# Microcontroller.net
KiCad netlist of a schematic drawn in Altium Designer
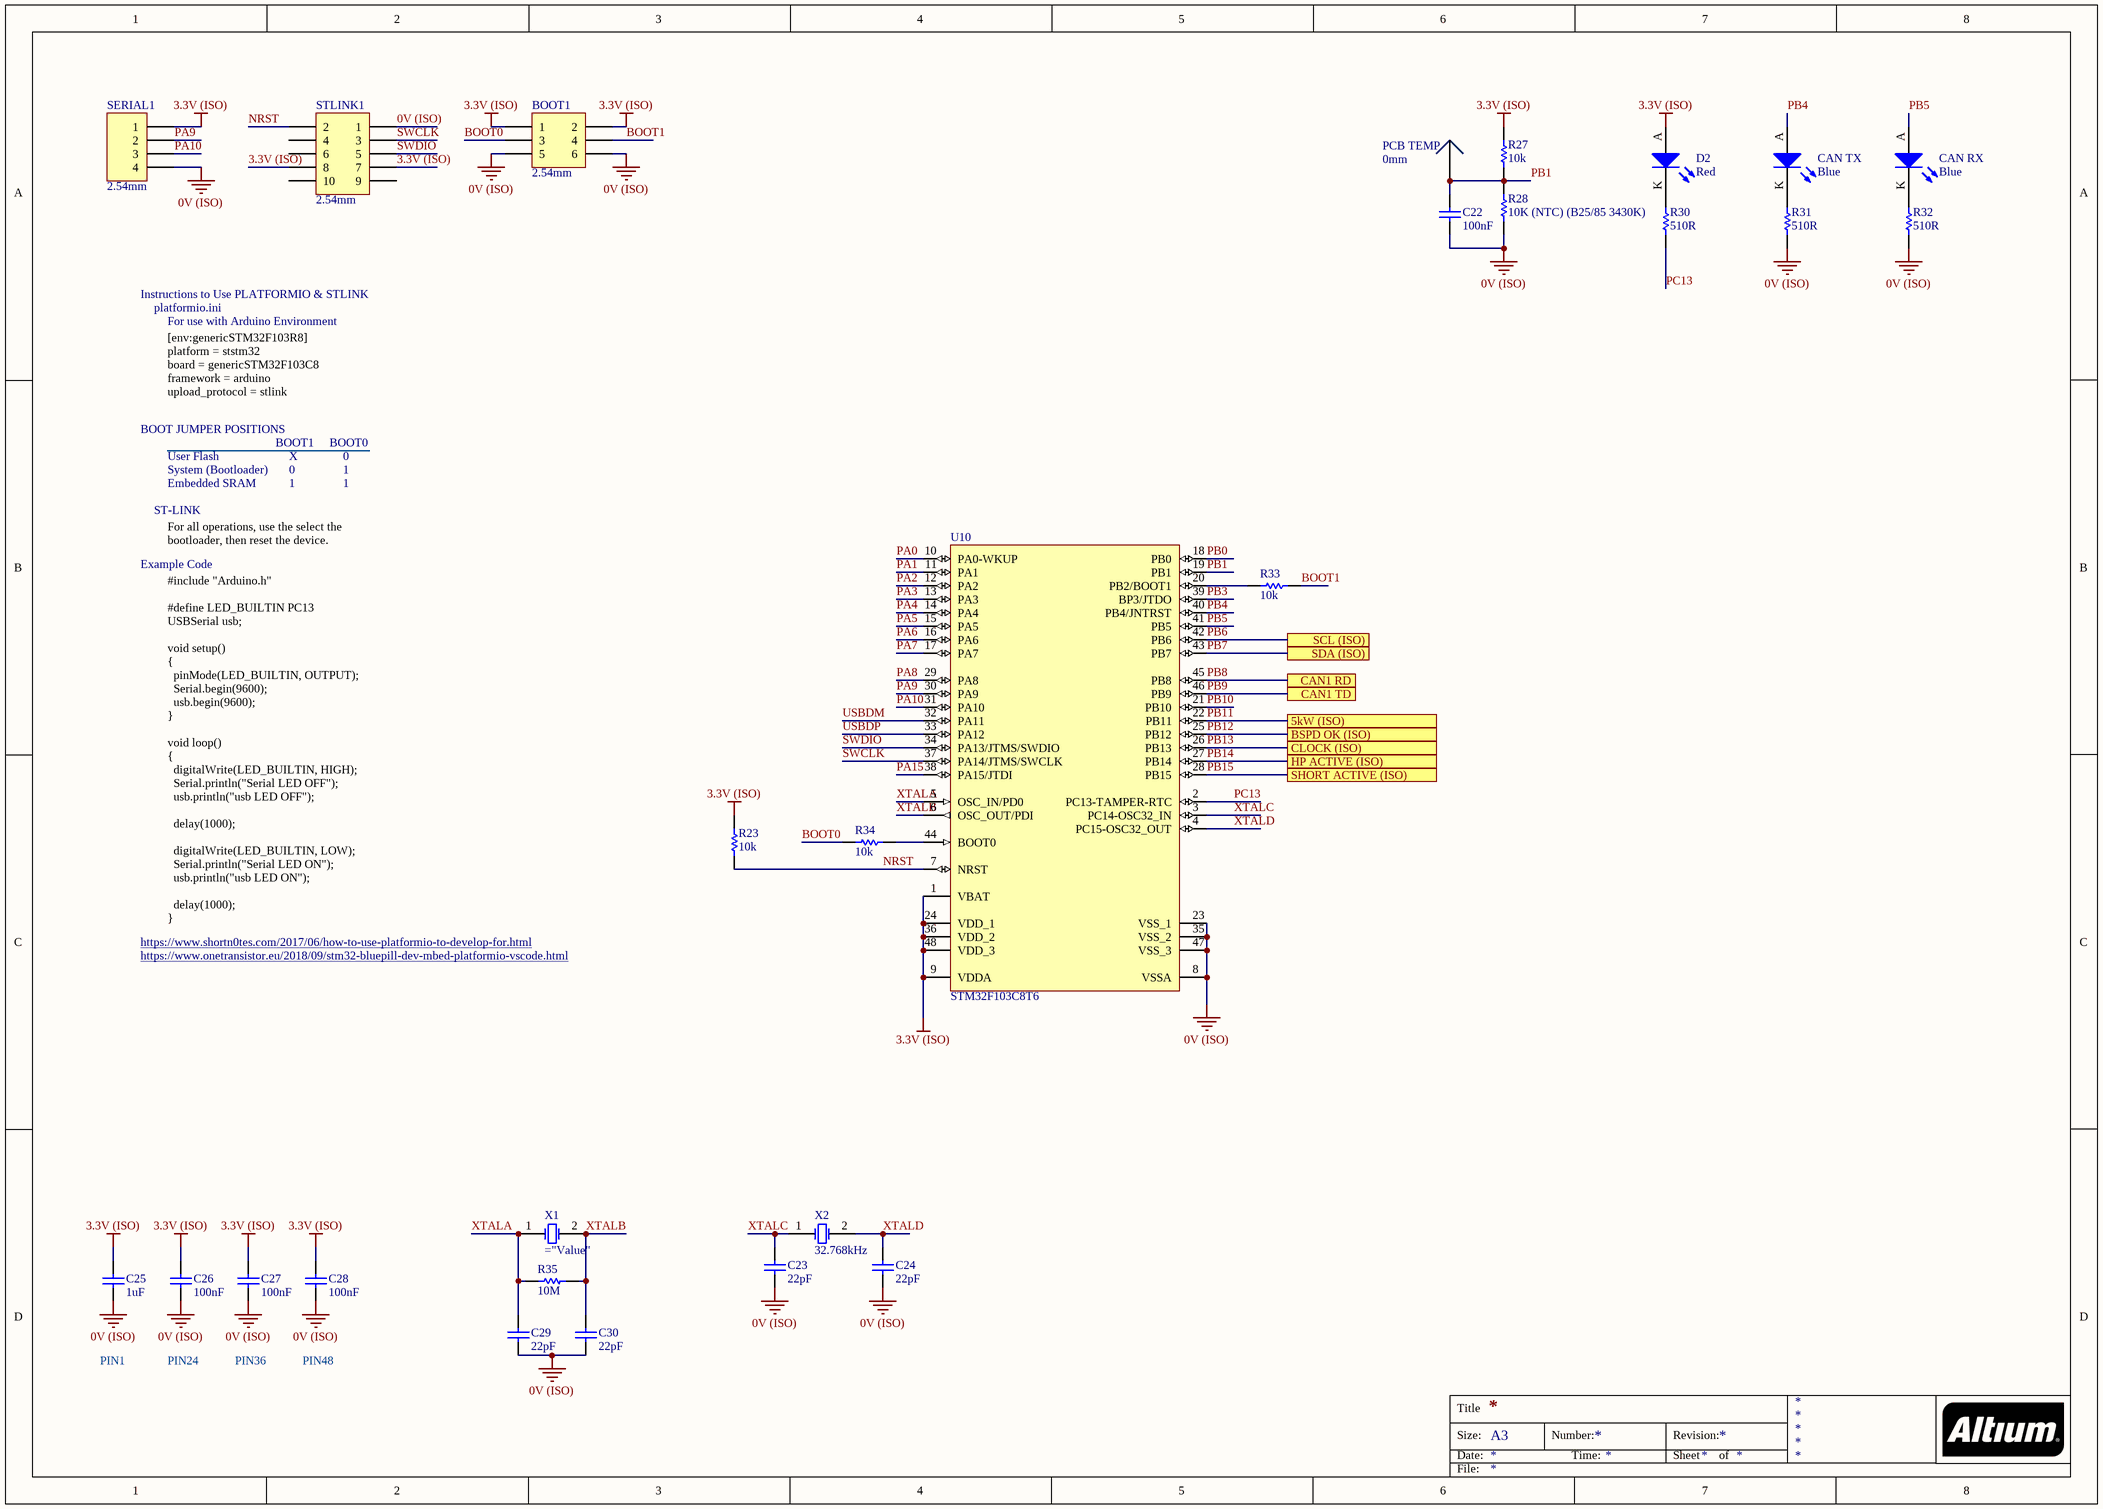
[diagram p0: Microcontroller.SchDoc]

(export (version "E")
  (design (tool "Eeschema 10.0.6"))
  (components
    (comp (ref "BOOT1")
      (value "2.54mm")
      (footprint "TH 2.54mm Header 2x3")
      (fields (field (name "PART NUMBER") "TH 2.54mm Header 2x3") (field (name "CONTACT") "NA"))
      (libsource (lib "ts_20-standard-connectors") (part "Header 2x3"))
    )
    (comp (ref "C22")
      (value "100nF")
      (footprint "0805")
      (fields
        (field (name "PART NUMBER") "GCM21BR71E104KA37L")
        (field (name "TOLERANCE") "10%")
        (field (name "MANUFACTURER") "muRata")
      )
      (libsource (lib "ts_20-standard-library") (part "Capacitor"))
    )
    (comp (ref "C23")
      (value "22pF")
      (footprint "0805")
      (fields
        (field (name "PART NUMBER") "GCM21B5C1H220JA37L")
        (field (name "TOLERANCE") "5%")
        (field (name "MANUFACTURER") "muRata")
      )
      (libsource (lib "ts_20-standard-library") (part "Capacitor"))
    )
    (comp (ref "C24")
      (value "22pF")
      (footprint "0805")
      (fields
        (field (name "PART NUMBER") "GCM21B5C1H220JA37L")
        (field (name "TOLERANCE") "5%")
        (field (name "MANUFACTURER") "muRata")
      )
      (libsource (lib "ts_20-standard-library") (part "Capacitor"))
    )
    (comp (ref "C25")
      (value "1uF")
      (footprint "0805")
      (fields
        (field (name "PART NUMBER") "GCM21BR71A105KA37L")
        (field (name "TOLERANCE") "10%")
        (field (name "MANUFACTURER") "muRata")
      )
      (libsource (lib "ts_20-standard-library") (part "Capacitor"))
    )
    (comp (ref "C26")
      (value "100nF")
      (footprint "0805")
      (fields
        (field (name "PART NUMBER") "GCM21BR71E104KA37L")
        (field (name "TOLERANCE") "10%")
        (field (name "MANUFACTURER") "muRata")
      )
      (libsource (lib "ts_20-standard-library") (part "Capacitor"))
    )
    (comp (ref "C27")
      (value "100nF")
      (footprint "0805")
      (fields
        (field (name "PART NUMBER") "GCM21BR71E104KA37L")
        (field (name "TOLERANCE") "10%")
        (field (name "MANUFACTURER") "muRata")
      )
      (libsource (lib "ts_20-standard-library") (part "Capacitor"))
    )
    (comp (ref "C28")
      (value "100nF")
      (footprint "0805")
      (fields
        (field (name "PART NUMBER") "GCM21BR71E104KA37L")
        (field (name "TOLERANCE") "10%")
        (field (name "MANUFACTURER") "muRata")
      )
      (libsource (lib "ts_20-standard-library") (part "Capacitor"))
    )
    (comp (ref "C29")
      (value "22pF")
      (footprint "0805")
      (fields
        (field (name "PART NUMBER") "GCM21B5C1H220JA37L")
        (field (name "TOLERANCE") "5%")
        (field (name "MANUFACTURER") "muRata")
      )
      (libsource (lib "ts_20-standard-library") (part "Capacitor"))
    )
    (comp (ref "C30")
      (value "22pF")
      (footprint "0805")
      (fields
        (field (name "PART NUMBER") "GCM21B5C1H220JA37L")
        (field (name "TOLERANCE") "5%")
        (field (name "MANUFACTURER") "muRata")
      )
      (libsource (lib "ts_20-standard-library") (part "Capacitor"))
    )
    (comp (ref "CAN RX")
      (value "Blue")
      (footprint "0805 LED")
      (description "LED BLUE CLEAR 2012 SMD")
      (fields
        (field (name "PART NUMBER") "SML-MN2BCTT86C")
        (field (name "MANUFACTURER") "ROHM Semiconductor")
      )
      (libsource (lib "ts_20-standard-library") (part "LED"))
    )
    (comp (ref "CAN TX")
      (value "Blue")
      (footprint "0805 LED")
      (description "LED BLUE CLEAR 2012 SMD")
      (fields
        (field (name "PART NUMBER") "SML-MN2BCTT86C")
        (field (name "MANUFACTURER") "ROHM Semiconductor")
      )
      (libsource (lib "ts_20-standard-library") (part "LED"))
    )
    (comp (ref "D2")
      (value "Red")
      (footprint "0805 LED")
      (description "Red LED Indication - Discrete 1.75V 0805 (2012 Metric)")
      (fields (field (name "PART NUMBER") "SML-210LTT86") (field (name "MANUFACTURER") "ROHM Semiconductor"))
      (libsource (lib "ts_20-standard-library") (part "LED"))
    )
    (comp (ref "PCB TEMP")
      (value "0mm")
      (footprint "SMD Test Point")
      (fields (field (name "PART NUMBER") "SMD Test Point") (field (name "CONTACT") "NA"))
      (libsource (lib "ts_20-standard-connectors") (part "Test Point"))
    )
    (comp (ref "R23")
      (value "10k")
      (footprint "0805")
      (fields
        (field (name "MANUFACTURER") "YAGEO")
        (field (name "PART NUMBER") "RC0805FR0710KL")
        (field (name "TOLERANCE") "0.01")
      )
      (libsource (lib "ts_20-standard-library") (part "Resistor"))
    )
    (comp (ref "R27")
      (value "10k")
      (footprint "0805")
      (fields
        (field (name "PART NUMBER") "RC0805FR0710KL")
        (field (name "MANUFACTURER") "YAGEO")
        (field (name "TOLERANCE") "0.01")
      )
      (libsource (lib "ts_20-standard-library") (part "Resistor"))
    )
    (comp (ref "R28")
      (value "10K (NTC) (B25/85 3430K)")
      (footprint "0805")
      (fields
        (field (name "PART NUMBER") "NTCS0805E3103FLT")
        (field (name "MANUFACTURER") "Vishay Beyschlag")
        (field (name "TOLERANCE") "0.01")
      )
      (libsource (lib "ts_20-standard-library") (part "Resistor"))
    )
    (comp (ref "R30")
      (value "510R")
      (footprint "0805")
      (fields
        (field (name "PART NUMBER") "RC0805FR07510RL")
        (field (name "MANUFACTURER") "YAGEO")
        (field (name "TOLERANCE") "0.01")
      )
      (libsource (lib "ts_20-standard-library") (part "Resistor"))
    )
    (comp (ref "R31")
      (value "510R")
      (footprint "0805")
      (fields
        (field (name "PART NUMBER") "RC0805FR07510RL")
        (field (name "MANUFACTURER") "YAGEO")
        (field (name "TOLERANCE") "0.01")
      )
      (libsource (lib "ts_20-standard-library") (part "Resistor"))
    )
    (comp (ref "R32")
      (value "510R")
      (footprint "0805")
      (fields
        (field (name "PART NUMBER") "RC0805FR07510RL")
        (field (name "MANUFACTURER") "YAGEO")
        (field (name "TOLERANCE") "0.01")
      )
      (libsource (lib "ts_20-standard-library") (part "Resistor"))
    )
    (comp (ref "R33")
      (value "10k")
      (footprint "0805")
      (fields
        (field (name "PART NUMBER") "RC0805FR0710KL")
        (field (name "MANUFACTURER") "YAGEO")
        (field (name "TOLERANCE") "0.01")
      )
      (libsource (lib "ts_20-standard-library") (part "Resistor"))
    )
    (comp (ref "R34")
      (value "10k")
      (footprint "0805")
      (fields
        (field (name "PART NUMBER") "RC0805FR0710KL")
        (field (name "MANUFACTURER") "YAGEO")
        (field (name "TOLERANCE") "0.01")
      )
      (libsource (lib "ts_20-standard-library") (part "Resistor"))
    )
    (comp (ref "R35")
      (value "10M")
      (footprint "0805")
      (fields
        (field (name "PART NUMBER") "RC0805FR0710ML")
        (field (name "MANUFACTURER") "YAGEO")
        (field (name "TOLERANCE") "0.01")
      )
      (libsource (lib "ts_20-standard-library") (part "Resistor"))
    )
    (comp (ref "SERIAL1")
      (value "2.54mm")
      (footprint "TH 2.54mm Header 1x4")
      (fields (field (name "PART NUMBER") "TH 2.54mm Header 1x4") (field (name "CONTACT") "NA"))
      (libsource (lib "ts_20-standard-connectors") (part "Header 1x4"))
    )
    (comp (ref "STLINK1")
      (value "2.54mm")
      (footprint "TH 2.54mm Header 2x5")
      (fields (field (name "PART NUMBER") "TH 2.54mm Header 2x5") (field (name "CONTACT") "NA"))
      (libsource (lib "ts_20-standard-connectors") (part "Header 2x5"))
    )
    (comp (ref "U10")
      (value "STM32F103C8T6")
      (footprint "STM 48-LQFP")
      (description "ARM® Cortex®-M3 STM32F1 Microcontroller IC 32-Bit 72MHz 64KB (64K x 8) FLASH")
      (fields
        (field (name "MANUFACTURER") "STMicroelectronics")
        (field (name "DIGIKEY PART NUMBER") "497-6063-ND")
      )
      (libsource (lib "ts_20-standard-library") (part "STM32F103C8T6"))
    )
    (comp (ref "X1")
      (value "~")
      (footprint "Abracon HC-49/US")
      (fields
        (field (name "PART NUMBER") "ABLS-16.000MHZ-B4-T")
        (field (name "MANUFACTURER") "Abracon LLC")
        (field (name "DIGIKEY PART NUMBER") "535-10226-1-ND")
      )
      (libsource (lib "ts_20-standard-library") (part "Crystal"))
    )
    (comp (ref "X2")
      (value "32.768kHz")
      (footprint "EPSON 2-SMD")
      (fields
        (field (name "PART NUMBER") "FC-135 32.7680KA-A5")
        (field (name "MANUFACTURER") "EPSON")
        (field (name "DIGIKEY PART NUMBER") "SER4103TR-ND")
      )
      (libsource (lib "ts_20-standard-library") (part "Crystal"))
    )
  )
  (nets
    (net (code "1") (name "/BOOT0") (class "Default")
      (node (ref "BOOT1") (pin "3") (pinfunction "3_3") (pintype "passive"))
      (node (ref "R34") (pin "1") (pinfunction "1_1") (pintype "passive"))
    )
    (net (code "2") (name "/BOOT1") (class "Default")
      (node (ref "BOOT1") (pin "4") (pinfunction "4_4") (pintype "passive"))
      (node (ref "R33") (pin "2") (pinfunction "2_2") (pintype "passive"))
    )
    (net (code "3") (name "/NRST") (class "Default")
      (node (ref "R23") (pin "1") (pinfunction "1_1") (pintype "passive"))
      (node (ref "STLINK1") (pin "2") (pinfunction "2_2") (pintype "passive"))
      (node (ref "U10") (pin "7") (pinfunction "NRST_7") (pintype "bidirectional"))
    )
    (net (code "4") (name "/PA0") (class "Default")
      (node (ref "U10") (pin "10") (pinfunction "PA0-WKUP_10") (pintype "bidirectional"))
    )
    (net (code "5") (name "/PA1") (class "Default")
      (node (ref "U10") (pin "11") (pinfunction "PA1_11") (pintype "bidirectional"))
    )
    (net (code "6") (name "/PA2") (class "Default")
      (node (ref "U10") (pin "12") (pinfunction "PA2_12") (pintype "bidirectional"))
    )
    (net (code "7") (name "/PA3") (class "Default")
      (node (ref "U10") (pin "13") (pinfunction "PA3_13") (pintype "bidirectional"))
    )
    (net (code "8") (name "/PA4") (class "Default")
      (node (ref "U10") (pin "14") (pinfunction "PA4_14") (pintype "bidirectional"))
    )
    (net (code "9") (name "/PA5") (class "Default")
      (node (ref "U10") (pin "15") (pinfunction "PA5_15") (pintype "bidirectional"))
    )
    (net (code "10") (name "/PA6") (class "Default")
      (node (ref "U10") (pin "16") (pinfunction "PA6_16") (pintype "bidirectional"))
    )
    (net (code "11") (name "/PA7") (class "Default")
      (node (ref "U10") (pin "17") (pinfunction "PA7_17") (pintype "bidirectional"))
    )
    (net (code "12") (name "/PA8") (class "Default")
      (node (ref "U10") (pin "29") (pinfunction "PA8_29") (pintype "bidirectional"))
    )
    (net (code "13") (name "/PA9") (class "Default")
      (node (ref "SERIAL1") (pin "2") (pinfunction "2_2") (pintype "passive"))
      (node (ref "U10") (pin "30") (pinfunction "PA9_30") (pintype "bidirectional"))
    )
    (net (code "14") (name "/PA10") (class "Default")
      (node (ref "SERIAL1") (pin "3") (pinfunction "3_3") (pintype "passive"))
      (node (ref "U10") (pin "31") (pinfunction "PA10_31") (pintype "bidirectional"))
    )
    (net (code "15") (name "/PA15") (class "Default")
      (node (ref "U10") (pin "38") (pinfunction "PA15/JTDI_38") (pintype "bidirectional"))
    )
    (net (code "16") (name "/PB0") (class "Default")
      (node (ref "U10") (pin "18") (pinfunction "PB0_18") (pintype "bidirectional"))
    )
    (net (code "17") (name "/PB1") (class "Default")
      (node (ref "C22") (pin "2") (pinfunction "2_2") (pintype "passive"))
      (node (ref "PCB TEMP") (pin "1") (pinfunction "1_1") (pintype "passive"))
      (node (ref "R27") (pin "1") (pinfunction "1_1") (pintype "passive"))
      (node (ref "R28") (pin "2") (pinfunction "2_2") (pintype "passive"))
      (node (ref "U10") (pin "19") (pinfunction "PB1_19") (pintype "bidirectional"))
    )
    (net (code "18") (name "/PB3") (class "Default")
      (node (ref "U10") (pin "39") (pinfunction "BP3/JTDO_39") (pintype "bidirectional"))
    )
    (net (code "19") (name "/PB4") (class "Default")
      (node (ref "CAN TX") (pin "A") (pinfunction "A_A") (pintype "passive"))
      (node (ref "U10") (pin "40") (pinfunction "PB4/JNTRST_40") (pintype "bidirectional"))
    )
    (net (code "20") (name "/PB5") (class "Default")
      (node (ref "CAN RX") (pin "A") (pinfunction "A_A") (pintype "passive"))
      (node (ref "U10") (pin "41") (pinfunction "PB5_41") (pintype "bidirectional"))
    )
    (net (code "21") (name "/PB6") (class "Default")
      (node (ref "U10") (pin "42") (pinfunction "PB6_42") (pintype "bidirectional"))
    )
    (net (code "22") (name "/PB7") (class "Default")
      (node (ref "U10") (pin "43") (pinfunction "PB7_43") (pintype "bidirectional"))
    )
    (net (code "23") (name "/PB8") (class "Default")
      (node (ref "U10") (pin "45") (pinfunction "PB8_45") (pintype "bidirectional"))
    )
    (net (code "24") (name "/PB9") (class "Default")
      (node (ref "U10") (pin "46") (pinfunction "PB9_46") (pintype "bidirectional"))
    )
    (net (code "25") (name "/PB10") (class "Default")
      (node (ref "U10") (pin "21") (pinfunction "PB10_21") (pintype "bidirectional"))
    )
    (net (code "26") (name "/PB11") (class "Default")
      (node (ref "U10") (pin "22") (pinfunction "PB11_22") (pintype "bidirectional"))
    )
    (net (code "27") (name "/PB12") (class "Default")
      (node (ref "U10") (pin "25") (pinfunction "PB12_25") (pintype "bidirectional"))
    )
    (net (code "28") (name "/PB13") (class "Default")
      (node (ref "U10") (pin "26") (pinfunction "PB13_26") (pintype "bidirectional"))
    )
    (net (code "29") (name "/PB14") (class "Default")
      (node (ref "U10") (pin "27") (pinfunction "PB14_27") (pintype "bidirectional"))
    )
    (net (code "30") (name "/PB15") (class "Default")
      (node (ref "U10") (pin "28") (pinfunction "PB15_28") (pintype "bidirectional"))
    )
    (net (code "31") (name "/PC13") (class "Default")
      (node (ref "R30") (pin "1") (pinfunction "1_1") (pintype "passive"))
      (node (ref "U10") (pin "2") (pinfunction "PC13-TAMPER-RTC_2") (pintype "bidirectional"))
    )
    (net (code "32") (name "/SWCLK") (class "Default")
      (node (ref "STLINK1") (pin "3") (pinfunction "3_3") (pintype "passive"))
      (node (ref "U10") (pin "37") (pinfunction "PA14/JTMS/SWCLK_37") (pintype "bidirectional"))
    )
    (net (code "33") (name "/SWDIO") (class "Default")
      (node (ref "STLINK1") (pin "5") (pinfunction "5_5") (pintype "passive"))
      (node (ref "U10") (pin "34") (pinfunction "PA13/JTMS/SWDIO_34") (pintype "bidirectional"))
    )
    (net (code "34") (name "/USBDM") (class "Default")
      (node (ref "U10") (pin "32") (pinfunction "PA11_32") (pintype "bidirectional"))
    )
    (net (code "35") (name "/USBDP") (class "Default")
      (node (ref "U10") (pin "33") (pinfunction "PA12_33") (pintype "bidirectional"))
    )
    (net (code "36") (name "/XTALA") (class "Default")
      (node (ref "C29") (pin "2") (pinfunction "2_2") (pintype "passive"))
      (node (ref "R35") (pin "1") (pinfunction "1_1") (pintype "passive"))
      (node (ref "U10") (pin "5") (pinfunction "OSC_IN/PD0_5") (pintype "input"))
      (node (ref "X1") (pin "1") (pinfunction "OSC1_1") (pintype "passive"))
    )
    (net (code "37") (name "/XTALB") (class "Default")
      (node (ref "C30") (pin "2") (pinfunction "2_2") (pintype "passive"))
      (node (ref "R35") (pin "2") (pinfunction "2_2") (pintype "passive"))
      (node (ref "U10") (pin "6") (pinfunction "OSC_OUT/PDI_6") (pintype "output"))
      (node (ref "X1") (pin "2") (pinfunction "OSC2_2") (pintype "passive"))
    )
    (net (code "38") (name "/XTALC") (class "Default")
      (node (ref "C23") (pin "2") (pinfunction "2_2") (pintype "passive"))
      (node (ref "U10") (pin "3") (pinfunction "PC14-OSC32_IN_3") (pintype "bidirectional"))
      (node (ref "X2") (pin "1") (pinfunction "OSC1_1") (pintype "passive"))
    )
    (net (code "39") (name "/XTALD") (class "Default")
      (node (ref "C24") (pin "2") (pinfunction "2_2") (pintype "passive"))
      (node (ref "U10") (pin "4") (pinfunction "PC15-OSC32_OUT_4") (pintype "bidirectional"))
      (node (ref "X2") (pin "2") (pinfunction "OSC2_2") (pintype "passive"))
    )
    (net (code "40") (name "0V (ISO)") (class "Default")
      (node (ref "BOOT1") (pin "5") (pinfunction "5_5") (pintype "passive"))
      (node (ref "BOOT1") (pin "6") (pinfunction "6_6") (pintype "passive"))
      (node (ref "C22") (pin "1") (pinfunction "1_1") (pintype "passive"))
      (node (ref "C23") (pin "1") (pinfunction "1_1") (pintype "passive"))
      (node (ref "C24") (pin "1") (pinfunction "1_1") (pintype "passive"))
      (node (ref "C25") (pin "1") (pinfunction "1_1") (pintype "passive"))
      (node (ref "C26") (pin "1") (pinfunction "1_1") (pintype "passive"))
      (node (ref "C27") (pin "1") (pinfunction "1_1") (pintype "passive"))
      (node (ref "C28") (pin "1") (pinfunction "1_1") (pintype "passive"))
      (node (ref "C29") (pin "1") (pinfunction "1_1") (pintype "passive"))
      (node (ref "C30") (pin "1") (pinfunction "1_1") (pintype "passive"))
      (node (ref "R28") (pin "1") (pinfunction "1_1") (pintype "passive"))
      (node (ref "R31") (pin "1") (pinfunction "1_1") (pintype "passive"))
      (node (ref "R32") (pin "1") (pinfunction "1_1") (pintype "passive"))
      (node (ref "SERIAL1") (pin "4") (pinfunction "4_4") (pintype "passive"))
      (node (ref "STLINK1") (pin "1") (pinfunction "1_1") (pintype "passive"))
      (node (ref "U10") (pin "23") (pinfunction "VSS_1_23") (pintype "power_in"))
      (node (ref "U10") (pin "35") (pinfunction "VSS_2_35") (pintype "power_in"))
      (node (ref "U10") (pin "47") (pinfunction "VSS_3_47") (pintype "power_in"))
      (node (ref "U10") (pin "8") (pinfunction "VSSA_8") (pintype "power_in"))
    )
    (net (code "41") (name "3.3V (ISO)") (class "Default")
      (node (ref "BOOT1") (pin "1") (pinfunction "1_1") (pintype "passive"))
      (node (ref "BOOT1") (pin "2") (pinfunction "2_2") (pintype "passive"))
      (node (ref "C25") (pin "2") (pinfunction "2_2") (pintype "passive"))
      (node (ref "C26") (pin "2") (pinfunction "2_2") (pintype "passive"))
      (node (ref "C27") (pin "2") (pinfunction "2_2") (pintype "passive"))
      (node (ref "C28") (pin "2") (pinfunction "2_2") (pintype "passive"))
      (node (ref "D2") (pin "A") (pinfunction "A_A") (pintype "passive"))
      (node (ref "R23") (pin "2") (pinfunction "2_2") (pintype "passive"))
      (node (ref "R27") (pin "2") (pinfunction "2_2") (pintype "passive"))
      (node (ref "SERIAL1") (pin "1") (pinfunction "1_1") (pintype "passive"))
      (node (ref "STLINK1") (pin "7") (pinfunction "7_7") (pintype "passive"))
      (node (ref "STLINK1") (pin "8") (pinfunction "8_8") (pintype "passive"))
      (node (ref "U10") (pin "1") (pinfunction "VBAT_1") (pintype "power_in"))
      (node (ref "U10") (pin "24") (pinfunction "VDD_1_24") (pintype "power_in"))
      (node (ref "U10") (pin "36") (pinfunction "VDD_2_36") (pintype "power_in"))
      (node (ref "U10") (pin "48") (pinfunction "VDD_3_48") (pintype "power_in"))
      (node (ref "U10") (pin "9") (pinfunction "VDDA_9") (pintype "power_in"))
    )
    (net (code "42") (name "Net-(CAN RX-PadK)") (class "Default")
      (node (ref "CAN RX") (pin "K") (pinfunction "K_K") (pintype "passive"))
      (node (ref "R32") (pin "2") (pinfunction "2_2") (pintype "passive"))
    )
    (net (code "43") (name "Net-(CAN TX-PadK)") (class "Default")
      (node (ref "CAN TX") (pin "K") (pinfunction "K_K") (pintype "passive"))
      (node (ref "R31") (pin "2") (pinfunction "2_2") (pintype "passive"))
    )
    (net (code "44") (name "Net-(D2-PadK)") (class "Default")
      (node (ref "D2") (pin "K") (pinfunction "K_K") (pintype "passive"))
      (node (ref "R30") (pin "2") (pinfunction "2_2") (pintype "passive"))
    )
    (net (code "45") (name "Net-(U10-BOOT0)") (class "Default")
      (node (ref "R34") (pin "2") (pinfunction "2_2") (pintype "passive"))
      (node (ref "U10") (pin "44") (pinfunction "BOOT0_44") (pintype "input"))
    )
    (net (code "46") (name "Net-(U10-PB2{slash}BOOT1)") (class "Default")
      (node (ref "R33") (pin "1") (pinfunction "1_1") (pintype "passive"))
      (node (ref "U10") (pin "20") (pinfunction "PB2/BOOT1_20") (pintype "bidirectional"))
    )
    (net (code "47") (name "unconnected-(STLINK1-Pad4)") (class "Default")
      (node (ref "STLINK1") (pin "4") (pinfunction "4_4") (pintype "passive"))
    )
    (net (code "48") (name "unconnected-(STLINK1-Pad6)") (class "Default")
      (node (ref "STLINK1") (pin "6") (pinfunction "6_6") (pintype "passive"))
    )
    (net (code "49") (name "unconnected-(STLINK1-Pad9)") (class "Default")
      (node (ref "STLINK1") (pin "9") (pinfunction "9_9") (pintype "passive"))
    )
    (net (code "50") (name "unconnected-(STLINK1-Pad10)") (class "Default")
      (node (ref "STLINK1") (pin "10") (pinfunction "10_10") (pintype "passive"))
    )
  )
)
